# button.net
KiCad netlist of a schematic drawn in Altium Designer
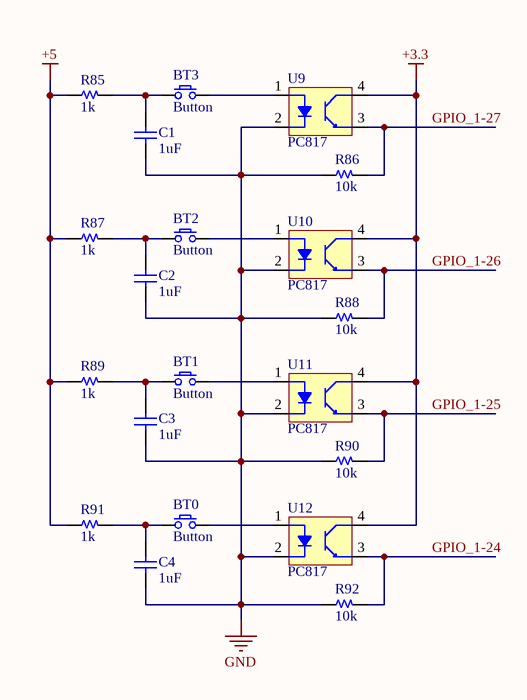
[diagram p0: button.SchDoc]

(export (version "E")
  (design (tool "Eeschema 10.0.6"))
  (components
    (comp (ref "BT0")
      (value "Button")
      (footprint "SW/4/SMD/XS")
      (description "Tact switch 2 pin")
      (libsource (lib "chipfc_libs") (part "SW SPST"))
    )
    (comp (ref "BT1")
      (value "Button")
      (footprint "SW/4/SMD/XS")
      (description "Tact switch 2 pin")
      (libsource (lib "chipfc_libs") (part "SW SPST"))
    )
    (comp (ref "BT2")
      (value "Button")
      (footprint "SW/4/SMD/XS")
      (description "Tact switch 2 pin")
      (libsource (lib "chipfc_libs") (part "SW SPST"))
    )
    (comp (ref "BT3")
      (value "Button")
      (footprint "SW/4/SMD/XS")
      (description "Tact switch 2 pin")
      (libsource (lib "chipfc_libs") (part "SW SPST"))
    )
    (comp (ref "C1")
      (value "1uF")
      (footprint "C 0603")
      (description "Capacitor non-pol")
      (libsource (lib "chipfc_libs") (part "Capacitor NP"))
    )
    (comp (ref "C2")
      (value "1uF")
      (footprint "C 0603")
      (description "Capacitor non-pol")
      (libsource (lib "chipfc_libs") (part "Capacitor NP"))
    )
    (comp (ref "C3")
      (value "1uF")
      (footprint "C 0603")
      (description "Capacitor non-pol")
      (libsource (lib "chipfc_libs") (part "Capacitor NP"))
    )
    (comp (ref "C4")
      (value "1uF")
      (footprint "C 0603")
      (description "Capacitor non-pol")
      (libsource (lib "chipfc_libs") (part "Capacitor NP"))
    )
    (comp (ref "R85")
      (value "1k")
      (footprint "R 0603")
      (description "Resistor")
      (libsource (lib "chipfc_libs") (part "Resistor"))
    )
    (comp (ref "R86")
      (value "10k")
      (footprint "R 0603")
      (description "Resistor")
      (libsource (lib "chipfc_libs") (part "Resistor"))
    )
    (comp (ref "R87")
      (value "1k")
      (footprint "R 0603")
      (description "Resistor")
      (libsource (lib "chipfc_libs") (part "Resistor"))
    )
    (comp (ref "R88")
      (value "10k")
      (footprint "R 0603")
      (description "Resistor")
      (libsource (lib "chipfc_libs") (part "Resistor"))
    )
    (comp (ref "R89")
      (value "1k")
      (footprint "R 0603")
      (description "Resistor")
      (libsource (lib "chipfc_libs") (part "Resistor"))
    )
    (comp (ref "R90")
      (value "10k")
      (footprint "R 0603")
      (description "Resistor")
      (libsource (lib "chipfc_libs") (part "Resistor"))
    )
    (comp (ref "R91")
      (value "1k")
      (footprint "R 0603")
      (description "Resistor")
      (libsource (lib "chipfc_libs") (part "Resistor"))
    )
    (comp (ref "R92")
      (value "10k")
      (footprint "R 0603")
      (description "Resistor")
      (libsource (lib "chipfc_libs") (part "Resistor"))
    )
    (comp (ref "U9")
      (value "PC817")
      (footprint "SOP4 - PC817")
      (description "Opto PC817B")
      (libsource (lib "bs_libs") (part "PC817"))
    )
    (comp (ref "U10")
      (value "PC817")
      (footprint "SOP4 - PC817")
      (description "Opto PC817B")
      (libsource (lib "bs_libs") (part "PC817"))
    )
    (comp (ref "U11")
      (value "PC817")
      (footprint "SOP4 - PC817")
      (description "Opto PC817B")
      (libsource (lib "bs_libs") (part "PC817"))
    )
    (comp (ref "U12")
      (value "PC817")
      (footprint "SOP4 - PC817")
      (description "Opto PC817B")
      (libsource (lib "bs_libs") (part "PC817"))
    )
  )
  (nets
    (net (code "1") (name "+3.3") (class "Default")
      (node (ref "U10") (pin "4") (pinfunction "C_4") (pintype "passive"))
      (node (ref "U11") (pin "4") (pinfunction "C_4") (pintype "passive"))
      (node (ref "U12") (pin "4") (pinfunction "C_4") (pintype "passive"))
      (node (ref "U9") (pin "4") (pinfunction "C_4") (pintype "passive"))
    )
    (net (code "2") (name "+5") (class "Default")
      (node (ref "R85") (pin "1") (pinfunction "1_1") (pintype "passive"))
      (node (ref "R87") (pin "1") (pinfunction "1_1") (pintype "passive"))
      (node (ref "R89") (pin "1") (pinfunction "1_1") (pintype "passive"))
      (node (ref "R91") (pin "1") (pinfunction "1_1") (pintype "passive"))
    )
    (net (code "3") (name "/GPIO_1-24") (class "Default")
      (node (ref "R92") (pin "2") (pinfunction "2_2") (pintype "passive"))
      (node (ref "U12") (pin "3") (pinfunction "E_3") (pintype "passive"))
    )
    (net (code "4") (name "/GPIO_1-25") (class "Default")
      (node (ref "R90") (pin "2") (pinfunction "2_2") (pintype "passive"))
      (node (ref "U11") (pin "3") (pinfunction "E_3") (pintype "passive"))
    )
    (net (code "5") (name "/GPIO_1-26") (class "Default")
      (node (ref "R88") (pin "2") (pinfunction "2_2") (pintype "passive"))
      (node (ref "U10") (pin "3") (pinfunction "E_3") (pintype "passive"))
    )
    (net (code "6") (name "/GPIO_1-27") (class "Default")
      (node (ref "R86") (pin "2") (pinfunction "2_2") (pintype "passive"))
      (node (ref "U9") (pin "3") (pinfunction "E_3") (pintype "passive"))
    )
    (net (code "7") (name "GND") (class "Default")
      (node (ref "C1") (pin "1") (pinfunction "1_1") (pintype "passive"))
      (node (ref "C2") (pin "1") (pinfunction "1_1") (pintype "passive"))
      (node (ref "C3") (pin "1") (pinfunction "1_1") (pintype "passive"))
      (node (ref "C4") (pin "1") (pinfunction "1_1") (pintype "passive"))
      (node (ref "R86") (pin "1") (pinfunction "1_1") (pintype "passive"))
      (node (ref "R88") (pin "1") (pinfunction "1_1") (pintype "passive"))
      (node (ref "R90") (pin "1") (pinfunction "1_1") (pintype "passive"))
      (node (ref "R92") (pin "1") (pinfunction "1_1") (pintype "passive"))
      (node (ref "U10") (pin "2") (pinfunction "K_2") (pintype "passive"))
      (node (ref "U11") (pin "2") (pinfunction "K_2") (pintype "passive"))
      (node (ref "U12") (pin "2") (pinfunction "K_2") (pintype "passive"))
      (node (ref "U9") (pin "2") (pinfunction "K_2") (pintype "passive"))
    )
    (net (code "8") (name "Net-(BT0-Pad1)") (class "Default")
      (node (ref "BT0") (pin "1") (pinfunction "1_1") (pintype "passive"))
      (node (ref "C4") (pin "2") (pinfunction "2_2") (pintype "passive"))
      (node (ref "R91") (pin "2") (pinfunction "2_2") (pintype "passive"))
    )
    (net (code "9") (name "Net-(BT1-Pad1)") (class "Default")
      (node (ref "BT1") (pin "1") (pinfunction "1_1") (pintype "passive"))
      (node (ref "C3") (pin "2") (pinfunction "2_2") (pintype "passive"))
      (node (ref "R89") (pin "2") (pinfunction "2_2") (pintype "passive"))
    )
    (net (code "10") (name "Net-(BT2-Pad1)") (class "Default")
      (node (ref "BT2") (pin "1") (pinfunction "1_1") (pintype "passive"))
      (node (ref "C2") (pin "2") (pinfunction "2_2") (pintype "passive"))
      (node (ref "R87") (pin "2") (pinfunction "2_2") (pintype "passive"))
    )
    (net (code "11") (name "Net-(BT3-Pad1)") (class "Default")
      (node (ref "BT3") (pin "1") (pinfunction "1_1") (pintype "passive"))
      (node (ref "C1") (pin "2") (pinfunction "2_2") (pintype "passive"))
      (node (ref "R85") (pin "2") (pinfunction "2_2") (pintype "passive"))
    )
    (net (code "12") (name "Net-(U9-A)") (class "Default")
      (node (ref "BT3") (pin "2") (pinfunction "2_2") (pintype "passive"))
      (node (ref "U9") (pin "1") (pinfunction "A_1") (pintype "passive"))
    )
    (net (code "13") (name "Net-(U10-A)") (class "Default")
      (node (ref "BT2") (pin "2") (pinfunction "2_2") (pintype "passive"))
      (node (ref "U10") (pin "1") (pinfunction "A_1") (pintype "passive"))
    )
    (net (code "14") (name "Net-(U11-A)") (class "Default")
      (node (ref "BT1") (pin "2") (pinfunction "2_2") (pintype "passive"))
      (node (ref "U11") (pin "1") (pinfunction "A_1") (pintype "passive"))
    )
    (net (code "15") (name "Net-(U12-A)") (class "Default")
      (node (ref "BT0") (pin "2") (pinfunction "2_2") (pintype "passive"))
      (node (ref "U12") (pin "1") (pinfunction "A_1") (pintype "passive"))
    )
  )
)
